# Toilet_Timer_V101.net
KiCad netlist of a schematic drawn in Altium Designer
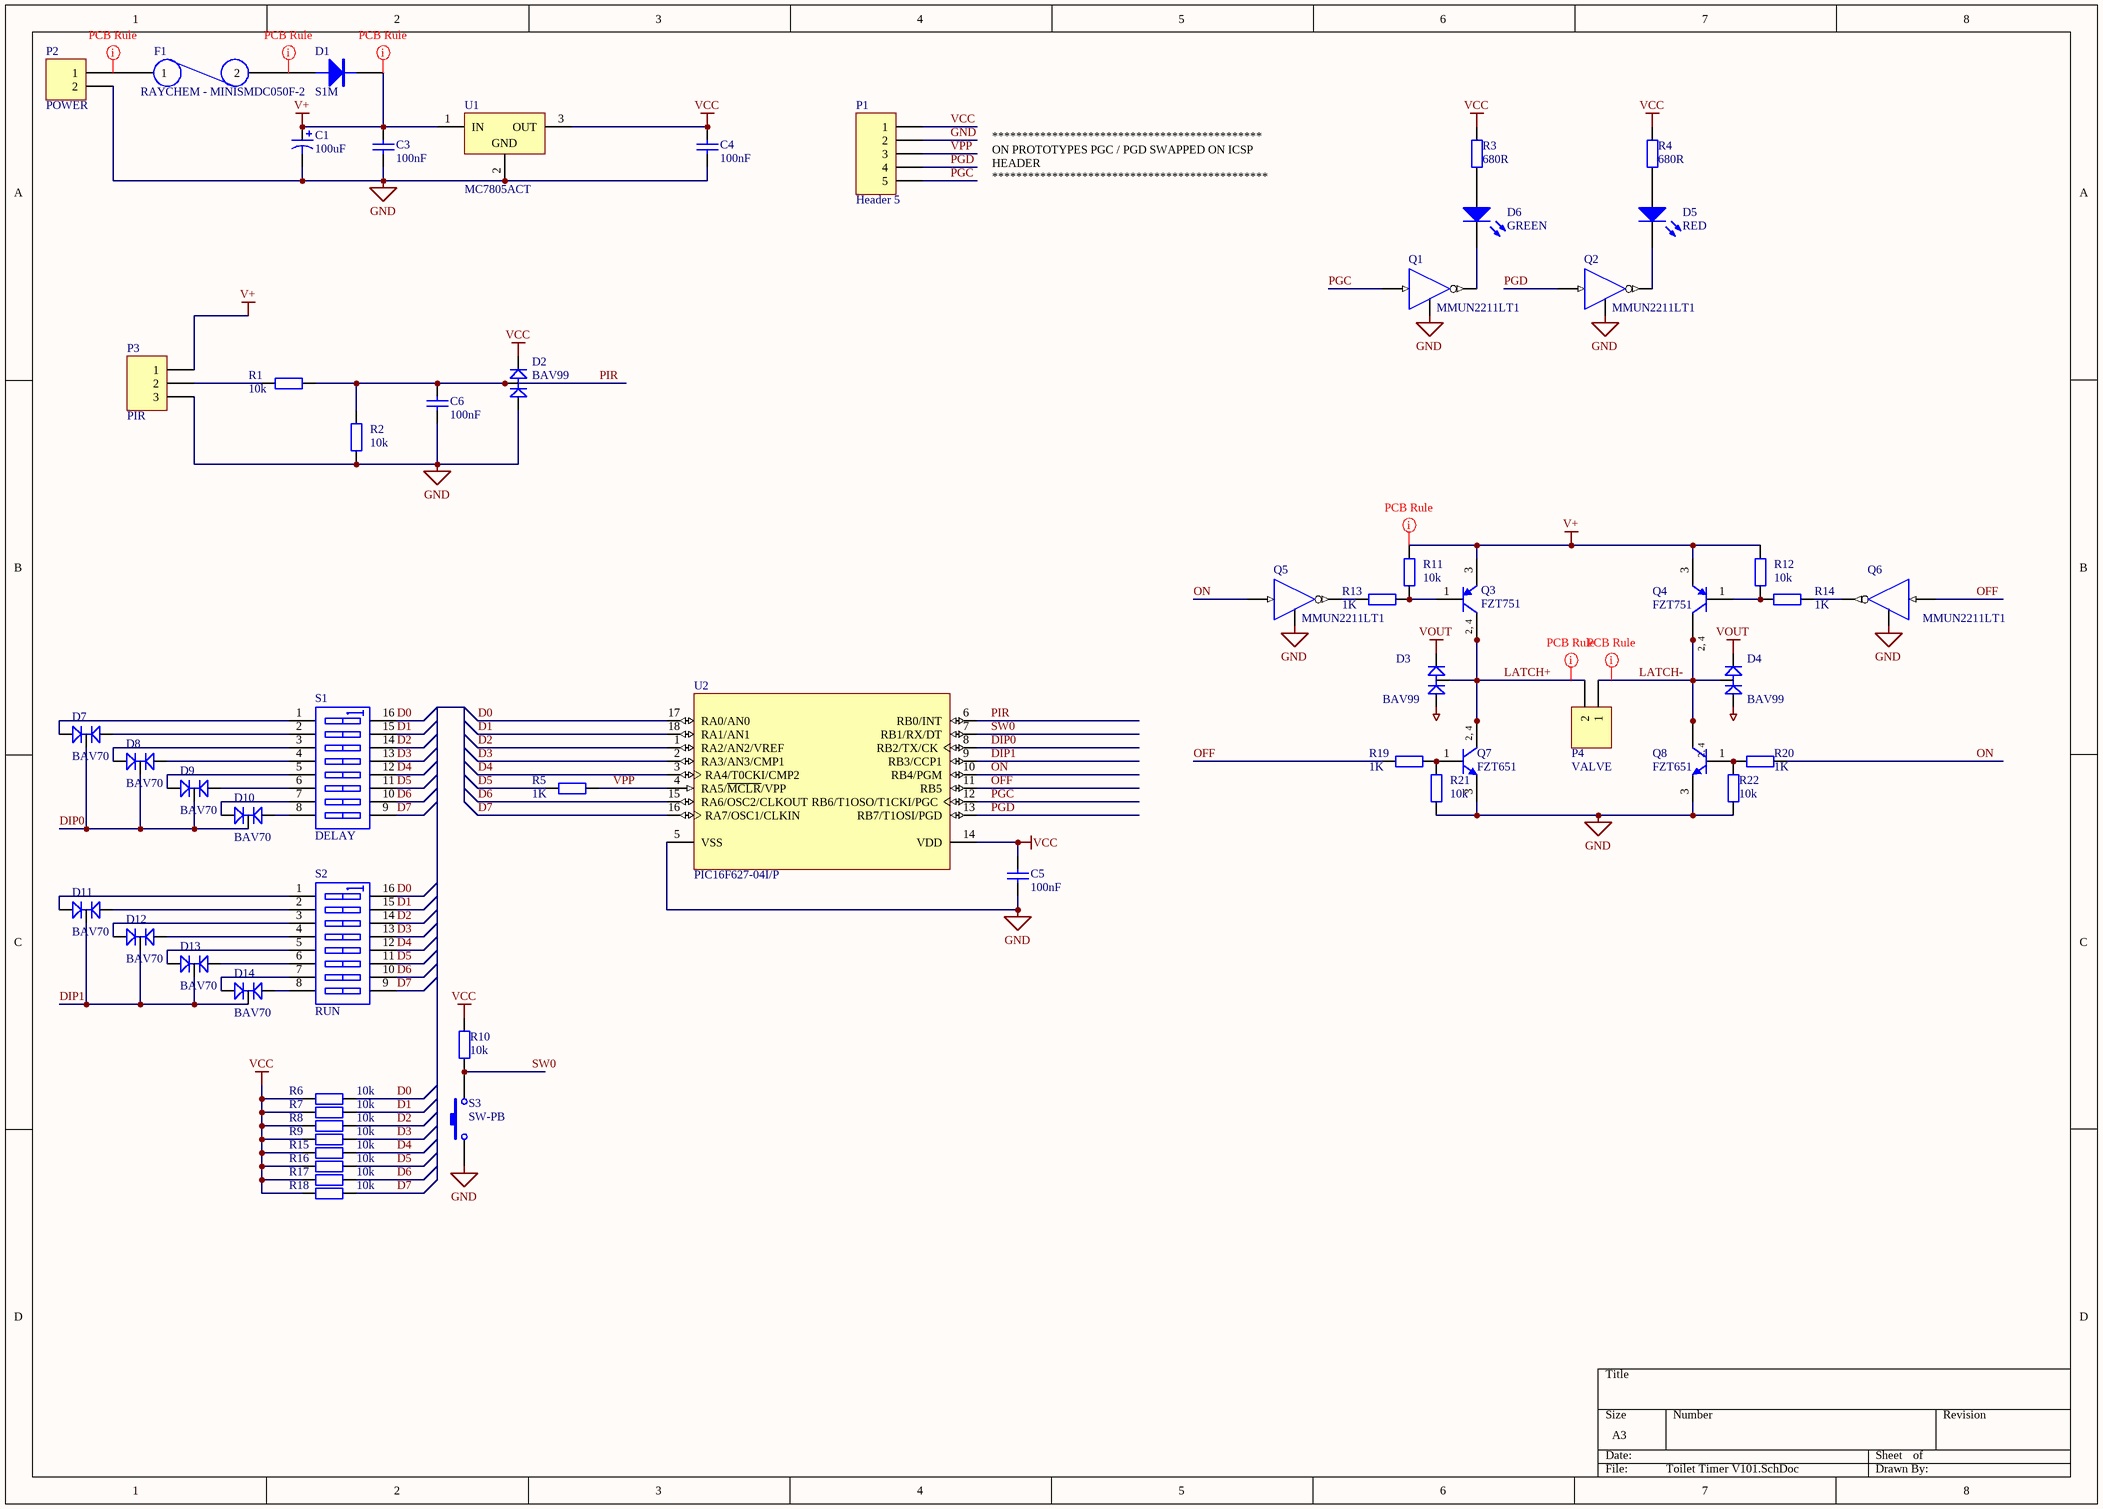
[diagram p0: Toilet Timer V101.SchDoc]

(export (version "E")
  (design (tool "Eeschema 10.0.6"))
  (components
    (comp (ref "C1")
      (value "100uF")
      (footprint "CAP, SMD E CASE")
      (description "Polarized Capacitor (Radial)")
      (fields (field (name "MOUSER PART NO.") "647-UVR1H101MPD1TA") (field (name "Comment") "Cap Pol1"))
      (libsource (lib "Miscellaneous Devices") (part "Cap Pol1"))
    )
    (comp (ref "C3")
      (value "100nF")
      (footprint "CAP(3D) - 0805")
      (description "Capacitor")
      (fields (field (name "MOUSER PART NO.") "K104Z15Y5VE5TH5") (field (name "Comment") "Cap"))
      (libsource (lib "Miscellaneous Devices") (part "Cap"))
    )
    (comp (ref "C4")
      (value "100nF")
      (footprint "CAP(3D) - 0805")
      (description "Capacitor")
      (fields (field (name "MOUSER PART NO.") "K104Z15Y5VE5TH5") (field (name "Comment") "Cap"))
      (libsource (lib "Miscellaneous Devices") (part "Cap"))
    )
    (comp (ref "C5")
      (value "100nF")
      (footprint "CAP(3D) - 0805")
      (description "Capacitor")
      (fields (field (name "MOUSER PART NO.") "K104Z15Y5VE5TH5") (field (name "Comment") "Cap"))
      (libsource (lib "Miscellaneous Devices") (part "Cap"))
    )
    (comp (ref "C6")
      (value "100nF")
      (footprint "CAP(3D) - 0805")
      (description "Capacitor")
      (fields (field (name "MOUSER PART NO.") "K104Z15Y5VE5TH5") (field (name "Comment") "Cap"))
      (libsource (lib "Miscellaneous Devices") (part "Cap"))
    )
    (comp (ref "D1")
      (value "S1M")
      (footprint "DO-214AC")
      (description "DIODE, POWER")
      (fields (field (name "MOUSER PART NO.") "821-S1M") (field (name "FARNELL PART NO.") "9843841"))
      (libsource (lib "401 CCPA") (part "DIODE"))
    )
    (comp (ref "D2")
      (value "BAV99")
      (footprint "SOT23-3L")
      (description "DUAL DIODE, BAV99")
      (fields (field (name "MOUSER PART NO.") "771-BAV99/T3") (field (name "FARNELL PART NO.") "9843612"))
      (libsource (lib "401 CCPA") (part "BAV99"))
    )
    (comp (ref "D3")
      (value "BAV99")
      (footprint "SOT23-3L")
      (description "DUAL DIODE, BAV99")
      (fields (field (name "MOUSER PART NO.") "771-BAV99/T3") (field (name "FARNELL PART NO.") "9843612"))
      (libsource (lib "401 CCPA") (part "BAV99"))
    )
    (comp (ref "D4")
      (value "BAV99")
      (footprint "SOT23-3L")
      (description "DUAL DIODE, BAV99")
      (fields (field (name "MOUSER PART NO.") "771-BAV99/T3") (field (name "FARNELL PART NO.") "9843612"))
      (libsource (lib "401 CCPA") (part "BAV99"))
    )
    (comp (ref "D5")
      (value "RED")
      (footprint "LED(3D) RED - 0805")
      (description "Typical INFRARED GaAs LED")
      (fields (field (name "MOUSER PART NO.") "606-4308H1"))
      (libsource (lib "Miscellaneous Devices") (part "LED0"))
    )
    (comp (ref "D6")
      (value "GREEN")
      (footprint "LED(3D) GREEN - 0805")
      (description "Typical INFRARED GaAs LED")
      (fields (field (name "MOUSER PART NO.") "606-4308H5"))
      (libsource (lib "Miscellaneous Devices") (part "LED0"))
    )
    (comp (ref "D7")
      (value "BAV70")
      (footprint "SOT23-3L")
      (description "DUAL DIODE, BAV99")
      (fields
        (field (name "FARNELL PART NO.") "9843612")
        (field (name "MANUFACTURER") "FAIRCHILD SEMICONDUCTOR")
      )
      (libsource (lib "Toilet Timer") (part "BAV70"))
    )
    (comp (ref "D8")
      (value "BAV70")
      (footprint "SOT23-3L")
      (description "DUAL DIODE, BAV99")
      (fields
        (field (name "FARNELL PART NO.") "9843612")
        (field (name "MANUFACTURER") "FAIRCHILD SEMICONDUCTOR")
      )
      (libsource (lib "Toilet Timer") (part "BAV70"))
    )
    (comp (ref "D9")
      (value "BAV70")
      (footprint "SOT23-3L")
      (description "DUAL DIODE, BAV99")
      (fields
        (field (name "FARNELL PART NO.") "9843612")
        (field (name "MANUFACTURER") "FAIRCHILD SEMICONDUCTOR")
      )
      (libsource (lib "Toilet Timer") (part "BAV70"))
    )
    (comp (ref "D10")
      (value "BAV70")
      (footprint "SOT23-3L")
      (description "DUAL DIODE, BAV99")
      (fields
        (field (name "FARNELL PART NO.") "9843612")
        (field (name "MANUFACTURER") "FAIRCHILD SEMICONDUCTOR")
      )
      (libsource (lib "Toilet Timer") (part "BAV70"))
    )
    (comp (ref "D11")
      (value "BAV70")
      (footprint "SOT23-3L")
      (description "DUAL DIODE, BAV99")
      (fields
        (field (name "FARNELL PART NO.") "9843612")
        (field (name "MANUFACTURER") "FAIRCHILD SEMICONDUCTOR")
      )
      (libsource (lib "Toilet Timer") (part "BAV70"))
    )
    (comp (ref "D12")
      (value "BAV70")
      (footprint "SOT23-3L")
      (description "DUAL DIODE, BAV99")
      (fields
        (field (name "FARNELL PART NO.") "9843612")
        (field (name "MANUFACTURER") "FAIRCHILD SEMICONDUCTOR")
      )
      (libsource (lib "Toilet Timer") (part "BAV70"))
    )
    (comp (ref "D13")
      (value "BAV70")
      (footprint "SOT23-3L")
      (description "DUAL DIODE, BAV99")
      (fields
        (field (name "FARNELL PART NO.") "9843612")
        (field (name "MANUFACTURER") "FAIRCHILD SEMICONDUCTOR")
      )
      (libsource (lib "Toilet Timer") (part "BAV70"))
    )
    (comp (ref "D14")
      (value "BAV70")
      (footprint "SOT23-3L")
      (description "DUAL DIODE, BAV99")
      (fields
        (field (name "FARNELL PART NO.") "9843612")
        (field (name "MANUFACTURER") "FAIRCHILD SEMICONDUCTOR")
      )
      (libsource (lib "Toilet Timer") (part "BAV70"))
    )
    (comp (ref "F1")
      (value "RAYCHEM - MINISMDC050F-2")
      (footprint "miniSMD Polyswitch")
      (fields
        (field (name "MOUSER PART NO.") "650-MINISMDC050F-2")
        (field (name "FARNELL PART NO.") "1175839")
        (field (name "MANUFACTURER") "Tyco Electronics / Raychem")
      )
      (libsource (lib "401 CCPA") (part "POLYSWITCH"))
    )
    (comp (ref "P1")
      (value "Header 5")
      (footprint "TERMINAL-6 POL")
      (description "Header, 5-Pin")
      (fields (field (name "MOUSER PART NO.") "571-6404565"))
      (libsource (lib "Miscellaneous Connectors") (part "Header 5"))
    )
    (comp (ref "P2")
      (value "POWER")
      (footprint "TYCO  1776112-2")
      (description "Header, 2-Pin")
      (fields (field (name "PUBLISHER") "Altium Limited"))
      (libsource (lib "Miscellaneous Connectors") (part "Header 2"))
    )
    (comp (ref "P3")
      (value "PIR")
      (footprint "TYCO  1776112-3")
      (description "Header, 3-Pin")
      (fields (field (name "PUBLISHER") "Altium Limited"))
      (libsource (lib "Miscellaneous Connectors") (part "Header 3"))
    )
    (comp (ref "P4")
      (value "VALVE")
      (footprint "TYCO  1776112-2")
      (description "Header, 2-Pin")
      (fields (field (name "PUBLISHER") "Altium Limited"))
      (libsource (lib "Miscellaneous Connectors") (part "Header 2"))
    )
    (comp (ref "Q1")
      (value "MMUN2211LT1")
      (footprint "SOT23-3L")
      (fields
        (field (name "MOUSER PART NO.") "863-MMUN2211LT1G")
        (field (name "FARNELL PART NO.") "9556648RL")
        (field (name "MANUFACTURER") "ON Semiconductor")
      )
      (libsource (lib "401 CCPA") (part "NPN DIGITAL TRANSISTOR"))
    )
    (comp (ref "Q2")
      (value "MMUN2211LT1")
      (footprint "SOT23-3L")
      (fields
        (field (name "MOUSER PART NO.") "863-MMUN2211LT1G")
        (field (name "FARNELL PART NO.") "9556648RL")
        (field (name "MANUFACTURER") "ON Semiconductor")
      )
      (libsource (lib "401 CCPA") (part "NPN DIGITAL TRANSISTOR"))
    )
    (comp (ref "Q3")
      (value "FZT751")
      (footprint "SOT223")
      (description "SOT223 PNP Silicon Planar High-Performance Transistor")
      (fields (field (name "PUBLISHER") "Altium Limited"))
      (libsource (lib "Zetex Discrete BJT") (part "FZT751"))
    )
    (comp (ref "Q4")
      (value "FZT751")
      (footprint "SOT223")
      (description "SOT223 PNP Silicon Planar High-Performance Transistor")
      (fields (field (name "PUBLISHER") "Altium Limited"))
      (libsource (lib "Zetex Discrete BJT") (part "FZT751"))
    )
    (comp (ref "Q5")
      (value "MMUN2211LT1")
      (footprint "SOT23-3L")
      (fields
        (field (name "MOUSER PART NO.") "863-MMUN2211LT1G")
        (field (name "FARNELL PART NO.") "9556648RL")
        (field (name "MANUFACTURER") "ON Semiconductor")
      )
      (libsource (lib "401 CCPA") (part "NPN DIGITAL TRANSISTOR"))
    )
    (comp (ref "Q6")
      (value "MMUN2211LT1")
      (footprint "SOT23-3L")
      (fields
        (field (name "MOUSER PART NO.") "863-MMUN2211LT1G")
        (field (name "FARNELL PART NO.") "9556648RL")
        (field (name "MANUFACTURER") "ON Semiconductor")
      )
      (libsource (lib "401 CCPA") (part "NPN DIGITAL TRANSISTOR"))
    )
    (comp (ref "Q7")
      (value "FZT651")
      (footprint "SOT223")
      (description "SOT223 NPN Silicon Planar High-Performance Transistor")
      (fields (field (name "PUBLISHER") "Altium Limited"))
      (libsource (lib "Zetex Discrete BJT") (part "FZT651"))
    )
    (comp (ref "Q8")
      (value "FZT651")
      (footprint "SOT223")
      (description "SOT223 NPN Silicon Planar High-Performance Transistor")
      (fields (field (name "PUBLISHER") "Altium Limited"))
      (libsource (lib "Zetex Discrete BJT") (part "FZT651"))
    )
    (comp (ref "R1")
      (value "10k")
      (footprint "RES(3D) - 0805")
      (description "Resistor")
      (fields (field (name "MOUSER PART NO.") "660-MF1/4LCT52R103J") (field (name "Comment") "Res2"))
      (libsource (lib "") (part "Res2_2"))
    )
    (comp (ref "R2")
      (value "10k")
      (footprint "RES(3D) - 0805")
      (description "Resistor")
      (fields (field (name "MOUSER PART NO.") "660-MF1/4LCT52R103J") (field (name "Comment") "Res2"))
      (libsource (lib "Miscellaneous Devices") (part "Res2"))
    )
    (comp (ref "R3")
      (value "680R")
      (footprint "RES(3D) - 0805")
      (description "Resistor")
      (fields (field (name "MOUSER PART NO.") "660-MF1/4DCT52R6800F") (field (name "Comment") "Res2"))
      (libsource (lib "Miscellaneous Devices") (part "Res2"))
    )
    (comp (ref "R4")
      (value "680R")
      (footprint "RES(3D) - 0805")
      (description "Resistor")
      (fields (field (name "MOUSER PART NO.") "660-MF1/4DCT52R6800F") (field (name "Comment") "Res2"))
      (libsource (lib "Miscellaneous Devices") (part "Res2"))
    )
    (comp (ref "R5")
      (value "1K")
      (footprint "RES(3D) - 0805")
      (description "Resistor")
      (fields (field (name "MOUSER PART NO.") "660-MF1/4DCT52R1102F") (field (name "Comment") "Res2"))
      (libsource (lib "") (part "Res2_2"))
    )
    (comp (ref "R6")
      (value "10k")
      (footprint "RES(3D) - 0805")
      (description "Resistor")
      (fields (field (name "MOUSER PART NO.") "660-MF1/4LCT52R103J") (field (name "Comment") "Res2"))
      (libsource (lib "") (part "Res2_1"))
    )
    (comp (ref "R7")
      (value "10k")
      (footprint "RES(3D) - 0805")
      (description "Resistor")
      (fields (field (name "MOUSER PART NO.") "660-MF1/4LCT52R103J") (field (name "Comment") "Res2"))
      (libsource (lib "") (part "Res2_1"))
    )
    (comp (ref "R8")
      (value "10k")
      (footprint "RES(3D) - 0805")
      (description "Resistor")
      (fields (field (name "MOUSER PART NO.") "660-MF1/4LCT52R103J") (field (name "Comment") "Res2"))
      (libsource (lib "") (part "Res2_1"))
    )
    (comp (ref "R9")
      (value "10k")
      (footprint "RES(3D) - 0805")
      (description "Resistor")
      (fields (field (name "MOUSER PART NO.") "660-MF1/4LCT52R103J") (field (name "Comment") "Res2"))
      (libsource (lib "") (part "Res2_1"))
    )
    (comp (ref "R10")
      (value "10k")
      (footprint "RES(3D) - 0805")
      (description "Resistor")
      (fields (field (name "MOUSER PART NO.") "660-MF1/4LCT52R103J") (field (name "Comment") "Res2"))
      (libsource (lib "") (part "Res2_3"))
    )
    (comp (ref "R11")
      (value "10k")
      (footprint "RES(3D) - 0805")
      (description "Resistor")
      (fields (field (name "MOUSER PART NO.") "660-MF1/4LCT52R103J") (field (name "Comment") "Res2"))
      (libsource (lib "Miscellaneous Devices") (part "Res2"))
    )
    (comp (ref "R12")
      (value "10k")
      (footprint "RES(3D) - 0805")
      (description "Resistor")
      (fields (field (name "MOUSER PART NO.") "660-MF1/4LCT52R103J") (field (name "Comment") "Res2"))
      (libsource (lib "Miscellaneous Devices") (part "Res2"))
    )
    (comp (ref "R13")
      (value "1K")
      (footprint "RES(3D) - 0805")
      (description "Resistor")
      (fields (field (name "MOUSER PART NO.") "660-MF1/4DCT52R1102F") (field (name "Comment") "Res2"))
      (libsource (lib "") (part "Res2_2"))
    )
    (comp (ref "R14")
      (value "1K")
      (footprint "RES(3D) - 0805")
      (description "Resistor")
      (fields (field (name "MOUSER PART NO.") "660-MF1/4DCT52R1102F") (field (name "Comment") "Res2"))
      (libsource (lib "") (part "Res2_3"))
    )
    (comp (ref "R15")
      (value "10k")
      (footprint "RES(3D) - 0805")
      (description "Resistor")
      (fields (field (name "MOUSER PART NO.") "660-MF1/4LCT52R103J") (field (name "Comment") "Res2"))
      (libsource (lib "") (part "Res2_1"))
    )
    (comp (ref "R16")
      (value "10k")
      (footprint "RES(3D) - 0805")
      (description "Resistor")
      (fields (field (name "MOUSER PART NO.") "660-MF1/4LCT52R103J") (field (name "Comment") "Res2"))
      (libsource (lib "") (part "Res2_1"))
    )
    (comp (ref "R17")
      (value "10k")
      (footprint "RES(3D) - 0805")
      (description "Resistor")
      (fields (field (name "MOUSER PART NO.") "660-MF1/4LCT52R103J") (field (name "Comment") "Res2"))
      (libsource (lib "") (part "Res2_1"))
    )
    (comp (ref "R18")
      (value "10k")
      (footprint "RES(3D) - 0805")
      (description "Resistor")
      (fields (field (name "MOUSER PART NO.") "660-MF1/4LCT52R103J") (field (name "Comment") "Res2"))
      (libsource (lib "") (part "Res2_1"))
    )
    (comp (ref "R19")
      (value "1K")
      (footprint "RES(3D) - 0805")
      (description "Resistor")
      (fields (field (name "MOUSER PART NO.") "660-MF1/4DCT52R1102F") (field (name "Comment") "Res2"))
      (libsource (lib "") (part "Res2_2"))
    )
    (comp (ref "R20")
      (value "1K")
      (footprint "RES(3D) - 0805")
      (description "Resistor")
      (fields (field (name "MOUSER PART NO.") "660-MF1/4DCT52R1102F") (field (name "Comment") "Res2"))
      (libsource (lib "") (part "Res2_3"))
    )
    (comp (ref "R21")
      (value "10k")
      (footprint "RES(3D) - 0805")
      (description "Resistor")
      (fields (field (name "MOUSER PART NO.") "660-MF1/4LCT52R103J") (field (name "Comment") "Res2"))
      (libsource (lib "Miscellaneous Devices") (part "Res2"))
    )
    (comp (ref "R22")
      (value "10k")
      (footprint "RES(3D) - 0805")
      (description "Resistor")
      (fields (field (name "MOUSER PART NO.") "660-MF1/4LCT52R103J") (field (name "Comment") "Res2"))
      (libsource (lib "") (part "Res2_2"))
    )
    (comp (ref "S1")
      (value "DELAY")
      (footprint "S-DIP-16")
      (description "DIP Switch, 8 Position, SPST")
      (fields (field (name "MOUSER PART NO.") "774-2068"))
      (libsource (lib "Miscellaneous Devices") (part "SW DIP-8"))
    )
    (comp (ref "S2")
      (value "RUN")
      (footprint "S-DIP-16")
      (description "DIP Switch, 8 Position, SPST")
      (fields (field (name "MOUSER PART NO.") "774-2068"))
      (libsource (lib "Miscellaneous Devices") (part "SW DIP-8"))
    )
    (comp (ref "S3")
      (value "SW-PB")
      (footprint "TACT 6MM")
      (description "Switch")
      (fields (field (name "MOUSER PART NO.") "642-MJTP1230"))
      (libsource (lib "Miscellaneous Devices") (part "SW-PB"))
    )
    (comp (ref "U1")
      (value "MC7805ACT")
      (footprint "7805 - DPAK")
      (description "3-Terminal Positive Fixed Voltage Regulator")
      (fields (field (name "MOUSER PART NO.") "512-LM7805ACT"))
      (libsource (lib "Motorola Power Mgt Voltage Regulator") (part "MC7805ACT"))
    )
    (comp (ref "U2")
      (value "PIC16F627-04I/P")
      (footprint "SOIC-18")
      (fields (field (name "MOUSER PART NO.") "579-PIC16F627A-I/P"))
      (libsource (lib "Microchip Microcontroller 8-Bit PIC16F") (part "PIC16F627-04I/P"))
    )
  )
  (nets
    (net (code "1") (name "/D0") (class "Default")
      (node (ref "R6") (pin "1") (pinfunction "1_1") (pintype "passive"))
      (node (ref "S1") (pin "16") (pinfunction "B1_16") (pintype "passive"))
      (node (ref "S2") (pin "16") (pinfunction "B1_16") (pintype "passive"))
      (node (ref "U2") (pin "17") (pinfunction "RA0/AN0_17") (pintype "bidirectional"))
    )
    (net (code "2") (name "/D1") (class "Default")
      (node (ref "R7") (pin "1") (pinfunction "1_1") (pintype "passive"))
      (node (ref "S1") (pin "15") (pinfunction "B2_15") (pintype "passive"))
      (node (ref "S2") (pin "15") (pinfunction "B2_15") (pintype "passive"))
      (node (ref "U2") (pin "18") (pinfunction "RA1/AN1_18") (pintype "bidirectional"))
    )
    (net (code "3") (name "/D2") (class "Default")
      (node (ref "R8") (pin "1") (pinfunction "1_1") (pintype "passive"))
      (node (ref "S1") (pin "14") (pinfunction "B3_14") (pintype "passive"))
      (node (ref "S2") (pin "14") (pinfunction "B3_14") (pintype "passive"))
      (node (ref "U2") (pin "1") (pinfunction "RA2/AN2/VREF_1") (pintype "bidirectional"))
    )
    (net (code "4") (name "/D3") (class "Default")
      (node (ref "R9") (pin "1") (pinfunction "1_1") (pintype "passive"))
      (node (ref "S1") (pin "13") (pinfunction "B4_13") (pintype "passive"))
      (node (ref "S2") (pin "13") (pinfunction "B4_13") (pintype "passive"))
      (node (ref "U2") (pin "2") (pinfunction "RA3/AN3/CMP1_2") (pintype "bidirectional"))
    )
    (net (code "5") (name "/D4") (class "Default")
      (node (ref "R15") (pin "1") (pinfunction "1_1") (pintype "passive"))
      (node (ref "S1") (pin "12") (pinfunction "B5_12") (pintype "passive"))
      (node (ref "S2") (pin "12") (pinfunction "B5_12") (pintype "passive"))
      (node (ref "U2") (pin "3") (pinfunction "RA4/T0CKI/CMP2_3") (pintype "bidirectional"))
    )
    (net (code "6") (name "/D5") (class "Default")
      (node (ref "R16") (pin "1") (pinfunction "1_1") (pintype "passive"))
      (node (ref "R5") (pin "1") (pinfunction "1_1") (pintype "passive"))
      (node (ref "S1") (pin "11") (pinfunction "B6_11") (pintype "passive"))
      (node (ref "S2") (pin "11") (pinfunction "B6_11") (pintype "passive"))
    )
    (net (code "7") (name "/D6") (class "Default")
      (node (ref "R17") (pin "1") (pinfunction "1_1") (pintype "passive"))
      (node (ref "S1") (pin "10") (pinfunction "B7_10") (pintype "passive"))
      (node (ref "S2") (pin "10") (pinfunction "B7_10") (pintype "passive"))
      (node (ref "U2") (pin "15") (pinfunction "RA6/OSC2/CLKOUT_15") (pintype "bidirectional"))
    )
    (net (code "8") (name "/D7") (class "Default")
      (node (ref "R18") (pin "1") (pinfunction "1_1") (pintype "passive"))
      (node (ref "S1") (pin "9") (pinfunction "B8_9") (pintype "passive"))
      (node (ref "S2") (pin "9") (pinfunction "B8_9") (pintype "passive"))
      (node (ref "U2") (pin "16") (pinfunction "RA7/OSC1/CLKIN_16") (pintype "bidirectional"))
    )
    (net (code "9") (name "/DIP0") (class "Default")
      (node (ref "D10") (pin "3") (pinfunction "C_3") (pintype "passive"))
      (node (ref "D7") (pin "3") (pinfunction "C_3") (pintype "passive"))
      (node (ref "D8") (pin "3") (pinfunction "C_3") (pintype "passive"))
      (node (ref "D9") (pin "3") (pinfunction "C_3") (pintype "passive"))
      (node (ref "U2") (pin "8") (pinfunction "RB2/TX/CK_8") (pintype "bidirectional"))
    )
    (net (code "10") (name "/DIP1") (class "Default")
      (node (ref "D11") (pin "3") (pinfunction "C_3") (pintype "passive"))
      (node (ref "D12") (pin "3") (pinfunction "C_3") (pintype "passive"))
      (node (ref "D13") (pin "3") (pinfunction "C_3") (pintype "passive"))
      (node (ref "D14") (pin "3") (pinfunction "C_3") (pintype "passive"))
      (node (ref "U2") (pin "9") (pinfunction "RB3/CCP1_9") (pintype "bidirectional"))
    )
    (net (code "11") (name "/LATCH+") (class "Default")
      (node (ref "D3") (pin "3") (pinfunction "C1/A2_3") (pintype "passive"))
      (node (ref "P4") (pin "2") (pinfunction "2_2") (pintype "passive"))
      (node (ref "Q3") (pin "2") (pinfunction "C_2") (pintype "passive"))
      (node (ref "Q3") (pin "4") (pinfunction "C_4") (pintype "passive"))
      (node (ref "Q7") (pin "2") (pinfunction "C_2") (pintype "passive"))
      (node (ref "Q7") (pin "4") (pinfunction "C_4") (pintype "passive"))
    )
    (net (code "12") (name "/LATCH-") (class "Default")
      (node (ref "D4") (pin "3") (pinfunction "C1/A2_3") (pintype "passive"))
      (node (ref "P4") (pin "1") (pinfunction "1_1") (pintype "passive"))
      (node (ref "Q4") (pin "2") (pinfunction "C_2") (pintype "passive"))
      (node (ref "Q4") (pin "4") (pinfunction "C_4") (pintype "passive"))
      (node (ref "Q8") (pin "2") (pinfunction "C_2") (pintype "passive"))
      (node (ref "Q8") (pin "4") (pinfunction "C_4") (pintype "passive"))
    )
    (net (code "13") (name "/OFF") (class "Default")
      (node (ref "Q6") (pin "1") (pinfunction "B_1") (pintype "input"))
      (node (ref "R19") (pin "1") (pinfunction "1_1") (pintype "passive"))
      (node (ref "U2") (pin "11") (pinfunction "RB5_11") (pintype "bidirectional"))
    )
    (net (code "14") (name "/ON") (class "Default")
      (node (ref "Q5") (pin "1") (pinfunction "B_1") (pintype "input"))
      (node (ref "R20") (pin "1") (pinfunction "1_1") (pintype "passive"))
      (node (ref "U2") (pin "10") (pinfunction "RB4/PGM_10") (pintype "bidirectional"))
    )
    (net (code "15") (name "/PGC") (class "Default")
      (node (ref "P1") (pin "5") (pinfunction "5_5") (pintype "passive"))
      (node (ref "Q1") (pin "1") (pinfunction "B_1") (pintype "input"))
      (node (ref "U2") (pin "12") (pinfunction "RB6/T1OSO/T1CKI/PGC_12") (pintype "bidirectional"))
    )
    (net (code "16") (name "/PGD") (class "Default")
      (node (ref "P1") (pin "4") (pinfunction "4_4") (pintype "passive"))
      (node (ref "Q2") (pin "1") (pinfunction "B_1") (pintype "input"))
      (node (ref "U2") (pin "13") (pinfunction "RB7/T1OSI/PGD_13") (pintype "bidirectional"))
    )
    (net (code "17") (name "/PIR") (class "Default")
      (node (ref "C6") (pin "2") (pinfunction "2_2") (pintype "passive"))
      (node (ref "D2") (pin "3") (pinfunction "C1/A2_3") (pintype "passive"))
      (node (ref "R1") (pin "2") (pinfunction "2_2") (pintype "passive"))
      (node (ref "R2") (pin "2") (pinfunction "2_2") (pintype "passive"))
      (node (ref "U2") (pin "6") (pinfunction "RB0/INT_6") (pintype "bidirectional"))
    )
    (net (code "18") (name "/SW0") (class "Default")
      (node (ref "R10") (pin "2") (pinfunction "2_2") (pintype "passive"))
      (node (ref "S3") (pin "2") (pinfunction "2_2") (pintype "passive"))
      (node (ref "U2") (pin "7") (pinfunction "RB1/RX/DT_7") (pintype "bidirectional"))
    )
    (net (code "19") (name "/VPP") (class "Default")
      (node (ref "P1") (pin "3") (pinfunction "3_3") (pintype "passive"))
      (node (ref "R5") (pin "2") (pinfunction "2_2") (pintype "passive"))
      (node (ref "U2") (pin "4") (pinfunction "RA5/~{MCLR}/VPP_4") (pintype "input"))
    )
    (net (code "20") (name "GND") (class "Default")
      (node (ref "C1") (pin "2") (pinfunction "2_2") (pintype "passive"))
      (node (ref "C3") (pin "1") (pinfunction "1_1") (pintype "passive"))
      (node (ref "C4") (pin "1") (pinfunction "1_1") (pintype "passive"))
      (node (ref "C5") (pin "1") (pinfunction "1_1") (pintype "passive"))
      (node (ref "C6") (pin "1") (pinfunction "1_1") (pintype "passive"))
      (node (ref "D2") (pin "1") (pinfunction "A1_1") (pintype "passive"))
      (node (ref "D3") (pin "1") (pinfunction "A1_1") (pintype "passive"))
      (node (ref "D4") (pin "1") (pinfunction "A1_1") (pintype "passive"))
      (node (ref "P1") (pin "2") (pinfunction "2_2") (pintype "passive"))
      (node (ref "P2") (pin "2") (pinfunction "2_2") (pintype "passive"))
      (node (ref "P3") (pin "3") (pinfunction "3_3") (pintype "passive"))
      (node (ref "Q1") (pin "2") (pinfunction "E_2") (pintype "passive"))
      (node (ref "Q2") (pin "2") (pinfunction "E_2") (pintype "passive"))
      (node (ref "Q5") (pin "2") (pinfunction "E_2") (pintype "passive"))
      (node (ref "Q6") (pin "2") (pinfunction "E_2") (pintype "passive"))
      (node (ref "Q7") (pin "3") (pinfunction "E_3") (pintype "passive"))
      (node (ref "Q8") (pin "3") (pinfunction "E_3") (pintype "passive"))
      (node (ref "R2") (pin "1") (pinfunction "1_1") (pintype "passive"))
      (node (ref "R21") (pin "1") (pinfunction "1_1") (pintype "passive"))
      (node (ref "R22") (pin "1") (pinfunction "1_1") (pintype "passive"))
      (node (ref "S3") (pin "1") (pinfunction "1_1") (pintype "passive"))
      (node (ref "U1") (pin "2") (pinfunction "GND_2") (pintype "power_in"))
      (node (ref "U2") (pin "5") (pinfunction "VSS_5") (pintype "power_in"))
    )
    (net (code "21") (name "Net-(D1-A)") (class "Default")
      (node (ref "D1") (pin "1") (pinfunction "A_1") (pintype "passive"))
      (node (ref "F1") (pin "2") (pinfunction "2_2") (pintype "passive"))
    )
    (net (code "22") (name "Net-(D5-A)") (class "Default")
      (node (ref "D5") (pin "1") (pinfunction "A_1") (pintype "passive"))
      (node (ref "R4") (pin "1") (pinfunction "1_1") (pintype "passive"))
    )
    (net (code "23") (name "Net-(D5-K)") (class "Default")
      (node (ref "D5") (pin "2") (pinfunction "K_2") (pintype "passive"))
      (node (ref "Q2") (pin "3") (pinfunction "C_3") (pintype "output"))
    )
    (net (code "24") (name "Net-(D6-A)") (class "Default")
      (node (ref "D6") (pin "1") (pinfunction "A_1") (pintype "passive"))
      (node (ref "R3") (pin "1") (pinfunction "1_1") (pintype "passive"))
    )
    (net (code "25") (name "Net-(D6-K)") (class "Default")
      (node (ref "D6") (pin "2") (pinfunction "K_2") (pintype "passive"))
      (node (ref "Q1") (pin "3") (pinfunction "C_3") (pintype "output"))
    )
    (net (code "26") (name "Net-(D7-A1)") (class "Default")
      (node (ref "D7") (pin "1") (pinfunction "A1_1") (pintype "passive"))
      (node (ref "S1") (pin "2") (pinfunction "A2_2") (pintype "passive"))
    )
    (net (code "27") (name "Net-(D7-A2)") (class "Default")
      (node (ref "D7") (pin "2") (pinfunction "A2_2") (pintype "passive"))
      (node (ref "S1") (pin "1") (pinfunction "A1_1") (pintype "passive"))
    )
    (net (code "28") (name "Net-(D8-A1)") (class "Default")
      (node (ref "D8") (pin "1") (pinfunction "A1_1") (pintype "passive"))
      (node (ref "S1") (pin "4") (pinfunction "A4_4") (pintype "passive"))
    )
    (net (code "29") (name "Net-(D8-A2)") (class "Default")
      (node (ref "D8") (pin "2") (pinfunction "A2_2") (pintype "passive"))
      (node (ref "S1") (pin "3") (pinfunction "A3_3") (pintype "passive"))
    )
    (net (code "30") (name "Net-(D9-A1)") (class "Default")
      (node (ref "D9") (pin "1") (pinfunction "A1_1") (pintype "passive"))
      (node (ref "S1") (pin "6") (pinfunction "A6_6") (pintype "passive"))
    )
    (net (code "31") (name "Net-(D9-A2)") (class "Default")
      (node (ref "D9") (pin "2") (pinfunction "A2_2") (pintype "passive"))
      (node (ref "S1") (pin "5") (pinfunction "A5_5") (pintype "passive"))
    )
    (net (code "32") (name "Net-(D10-A1)") (class "Default")
      (node (ref "D10") (pin "1") (pinfunction "A1_1") (pintype "passive"))
      (node (ref "S1") (pin "8") (pinfunction "A8_8") (pintype "passive"))
    )
    (net (code "33") (name "Net-(D10-A2)") (class "Default")
      (node (ref "D10") (pin "2") (pinfunction "A2_2") (pintype "passive"))
      (node (ref "S1") (pin "7") (pinfunction "A7_7") (pintype "passive"))
    )
    (net (code "34") (name "Net-(D11-A1)") (class "Default")
      (node (ref "D11") (pin "1") (pinfunction "A1_1") (pintype "passive"))
      (node (ref "S2") (pin "2") (pinfunction "A2_2") (pintype "passive"))
    )
    (net (code "35") (name "Net-(D11-A2)") (class "Default")
      (node (ref "D11") (pin "2") (pinfunction "A2_2") (pintype "passive"))
      (node (ref "S2") (pin "1") (pinfunction "A1_1") (pintype "passive"))
    )
    (net (code "36") (name "Net-(D12-A1)") (class "Default")
      (node (ref "D12") (pin "1") (pinfunction "A1_1") (pintype "passive"))
      (node (ref "S2") (pin "4") (pinfunction "A4_4") (pintype "passive"))
    )
    (net (code "37") (name "Net-(D12-A2)") (class "Default")
      (node (ref "D12") (pin "2") (pinfunction "A2_2") (pintype "passive"))
      (node (ref "S2") (pin "3") (pinfunction "A3_3") (pintype "passive"))
    )
    (net (code "38") (name "Net-(D13-A1)") (class "Default")
      (node (ref "D13") (pin "1") (pinfunction "A1_1") (pintype "passive"))
      (node (ref "S2") (pin "6") (pinfunction "A6_6") (pintype "passive"))
    )
    (net (code "39") (name "Net-(D13-A2)") (class "Default")
      (node (ref "D13") (pin "2") (pinfunction "A2_2") (pintype "passive"))
      (node (ref "S2") (pin "5") (pinfunction "A5_5") (pintype "passive"))
    )
    (net (code "40") (name "Net-(D14-A1)") (class "Default")
      (node (ref "D14") (pin "1") (pinfunction "A1_1") (pintype "passive"))
      (node (ref "S2") (pin "8") (pinfunction "A8_8") (pintype "passive"))
    )
    (net (code "41") (name "Net-(D14-A2)") (class "Default")
      (node (ref "D14") (pin "2") (pinfunction "A2_2") (pintype "passive"))
      (node (ref "S2") (pin "7") (pinfunction "A7_7") (pintype "passive"))
    )
    (net (code "42") (name "Net-(F1-Pad1)") (class "Default")
      (node (ref "F1") (pin "1") (pinfunction "1_1") (pintype "passive"))
      (node (ref "P2") (pin "1") (pinfunction "1_1") (pintype "passive"))
    )
    (net (code "43") (name "Net-(P3-Pad2)") (class "Default")
      (node (ref "P3") (pin "2") (pinfunction "2_2") (pintype "passive"))
      (node (ref "R1") (pin "1") (pinfunction "1_1") (pintype "passive"))
    )
    (net (code "44") (name "Net-(Q3-B)") (class "Default")
      (node (ref "Q3") (pin "1") (pinfunction "B_1") (pintype "passive"))
      (node (ref "R11") (pin "1") (pinfunction "1_1") (pintype "passive"))
      (node (ref "R13") (pin "2") (pinfunction "2_2") (pintype "passive"))
    )
    (net (code "45") (name "Net-(Q4-B)") (class "Default")
      (node (ref "Q4") (pin "1") (pinfunction "B_1") (pintype "passive"))
      (node (ref "R12") (pin "1") (pinfunction "1_1") (pintype "passive"))
      (node (ref "R14") (pin "2") (pinfunction "2_2") (pintype "passive"))
    )
    (net (code "46") (name "Net-(Q5-C)") (class "Default")
      (node (ref "Q5") (pin "3") (pinfunction "C_3") (pintype "output"))
      (node (ref "R13") (pin "1") (pinfunction "1_1") (pintype "passive"))
    )
    (net (code "47") (name "Net-(Q6-C)") (class "Default")
      (node (ref "Q6") (pin "3") (pinfunction "C_3") (pintype "output"))
      (node (ref "R14") (pin "1") (pinfunction "1_1") (pintype "passive"))
    )
    (net (code "48") (name "Net-(Q7-B)") (class "Default")
      (node (ref "Q7") (pin "1") (pinfunction "B_1") (pintype "passive"))
      (node (ref "R19") (pin "2") (pinfunction "2_2") (pintype "passive"))
      (node (ref "R21") (pin "2") (pinfunction "2_2") (pintype "passive"))
    )
    (net (code "49") (name "Net-(Q8-B)") (class "Default")
      (node (ref "Q8") (pin "1") (pinfunction "B_1") (pintype "passive"))
      (node (ref "R20") (pin "2") (pinfunction "2_2") (pintype "passive"))
      (node (ref "R22") (pin "2") (pinfunction "2_2") (pintype "passive"))
    )
    (net (code "50") (name "V+") (class "Default")
      (node (ref "C1") (pin "1") (pinfunction "1_1") (pintype "passive"))
      (node (ref "C3") (pin "2") (pinfunction "2_2") (pintype "passive"))
      (node (ref "D1") (pin "2") (pinfunction "K_2") (pintype "passive"))
      (node (ref "P3") (pin "1") (pinfunction "1_1") (pintype "passive"))
      (node (ref "Q3") (pin "3") (pinfunction "E_3") (pintype "passive"))
      (node (ref "Q4") (pin "3") (pinfunction "E_3") (pintype "passive"))
      (node (ref "R11") (pin "2") (pinfunction "2_2") (pintype "passive"))
      (node (ref "R12") (pin "2") (pinfunction "2_2") (pintype "passive"))
      (node (ref "U1") (pin "1") (pinfunction "IN_1") (pintype "power_in"))
    )
    (net (code "51") (name "VCC") (class "Default")
      (node (ref "C4") (pin "2") (pinfunction "2_2") (pintype "passive"))
      (node (ref "C5") (pin "2") (pinfunction "2_2") (pintype "passive"))
      (node (ref "D2") (pin "2") (pinfunction "C2_2") (pintype "passive"))
      (node (ref "P1") (pin "1") (pinfunction "1_1") (pintype "passive"))
      (node (ref "R10") (pin "1") (pinfunction "1_1") (pintype "passive"))
      (node (ref "R15") (pin "2") (pinfunction "2_2") (pintype "passive"))
      (node (ref "R16") (pin "2") (pinfunction "2_2") (pintype "passive"))
      (node (ref "R17") (pin "2") (pinfunction "2_2") (pintype "passive"))
      (node (ref "R18") (pin "2") (pinfunction "2_2") (pintype "passive"))
      (node (ref "R3") (pin "2") (pinfunction "2_2") (pintype "passive"))
      (node (ref "R4") (pin "2") (pinfunction "2_2") (pintype "passive"))
      (node (ref "R6") (pin "2") (pinfunction "2_2") (pintype "passive"))
      (node (ref "R7") (pin "2") (pinfunction "2_2") (pintype "passive"))
      (node (ref "R8") (pin "2") (pinfunction "2_2") (pintype "passive"))
      (node (ref "R9") (pin "2") (pinfunction "2_2") (pintype "passive"))
      (node (ref "U1") (pin "3") (pinfunction "OUT_3") (pintype "power_in"))
      (node (ref "U2") (pin "14") (pinfunction "VDD_14") (pintype "power_in"))
    )
    (net (code "52") (name "VOUT") (class "Default")
      (node (ref "D3") (pin "2") (pinfunction "C2_2") (pintype "passive"))
      (node (ref "D4") (pin "2") (pinfunction "C2_2") (pintype "passive"))
    )
  )
)
